# Adafruit_TMC2209_Stepper_Motor_Driver.net
KiCad netlist of a schematic drawn in EAGLE
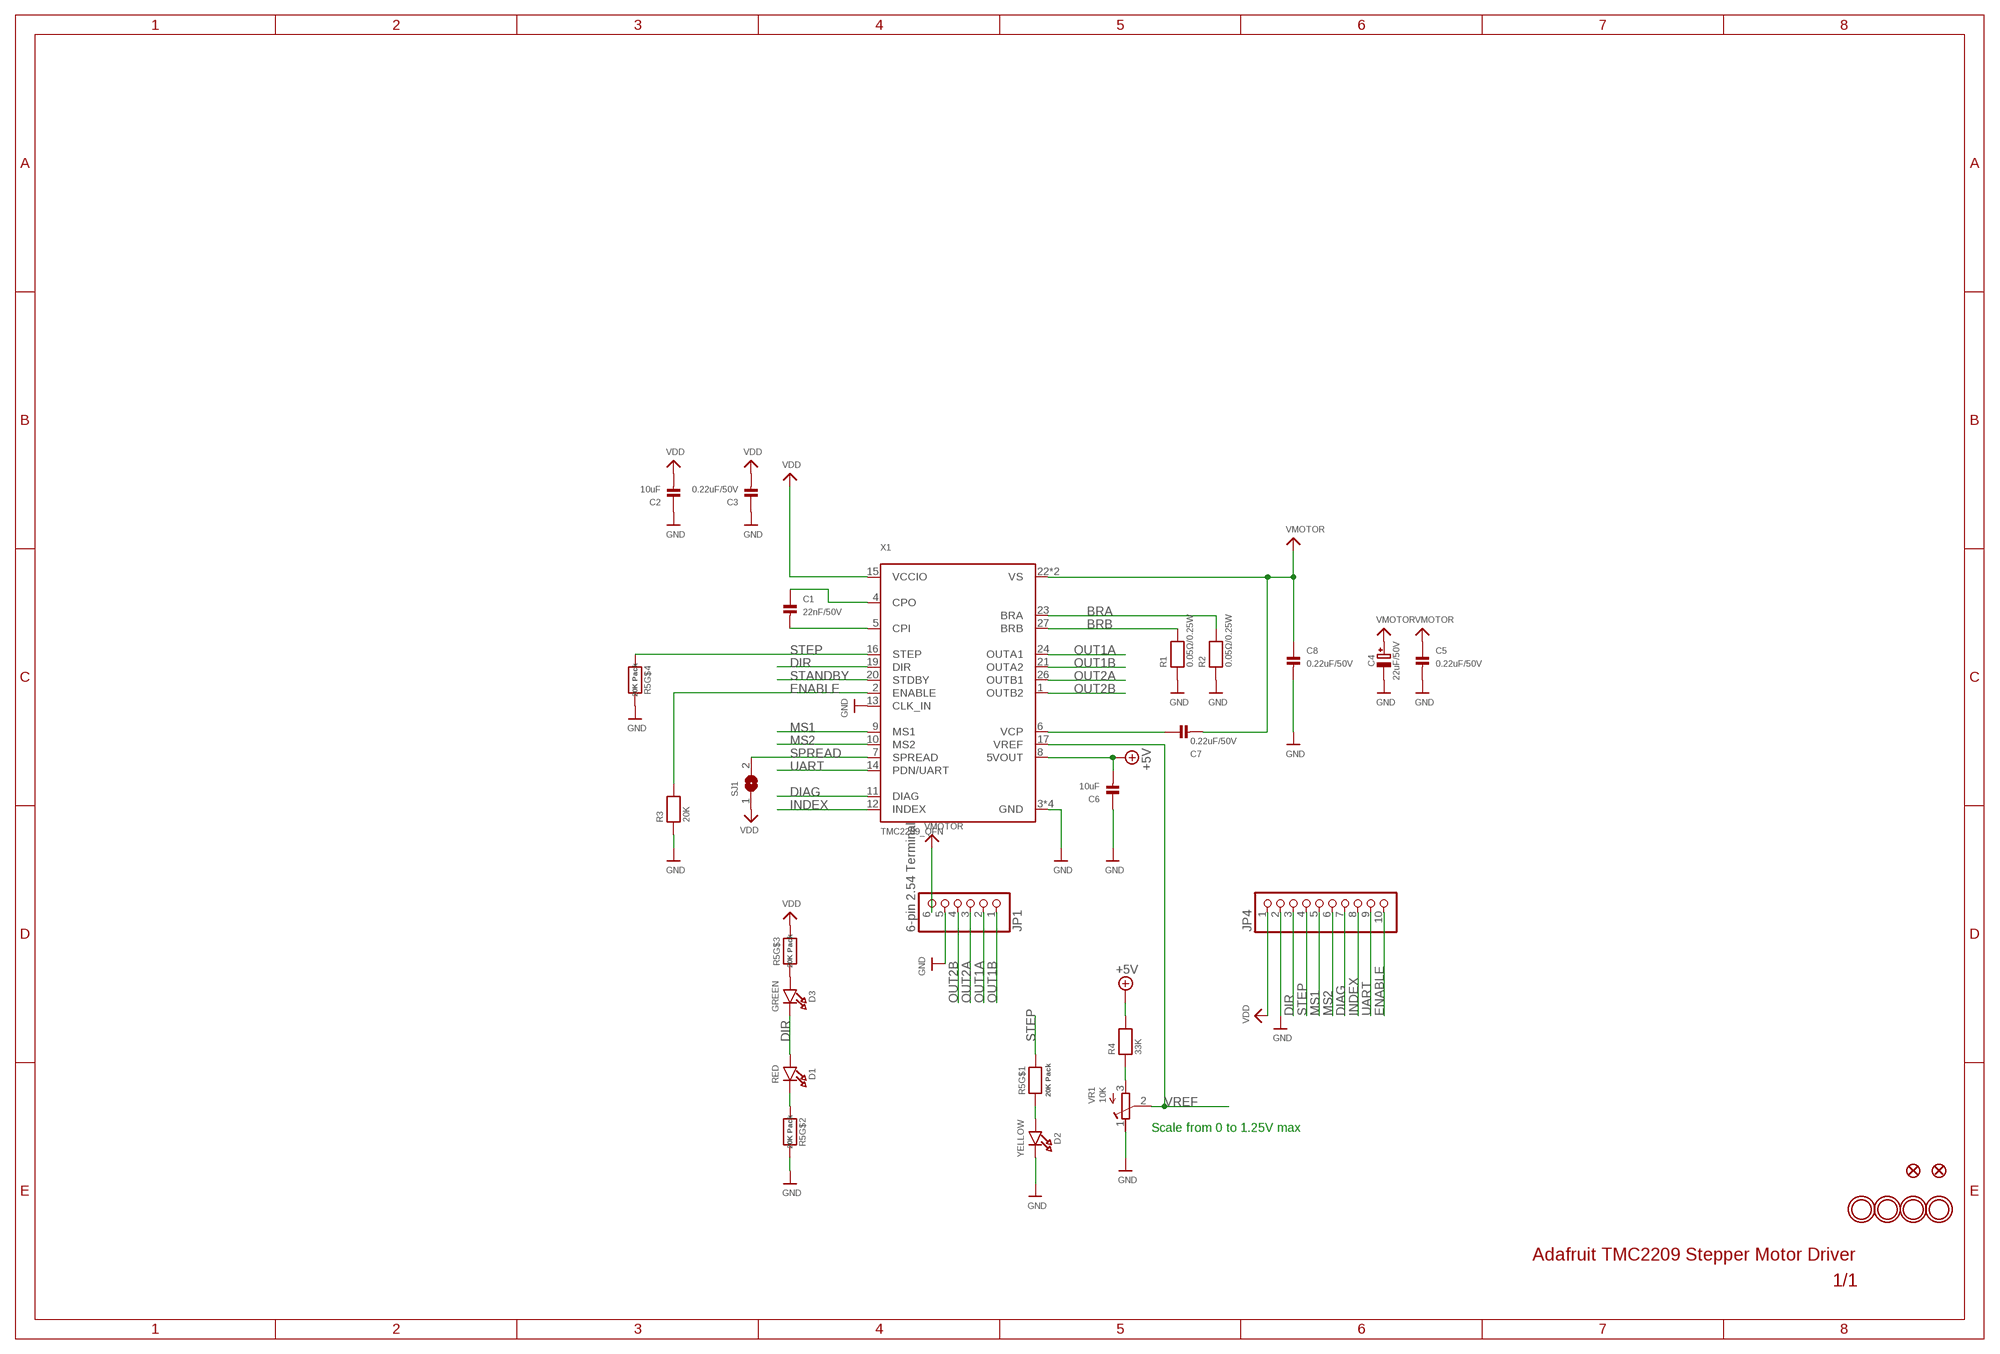
[diagram p0: schematic, sheet 1]

(export (version "E")
  (design (tool "Eeschema 10.0.6"))
  (components
    (comp (ref "C1")
      (value "22nF/50V")
      (footprint "eagle-import:0603-NO")
      (libsource (lib "eagle-import") (part "CAP_CERAMIC0603_NO"))
    )
    (comp (ref "C2")
      (value "10uF")
      (footprint "eagle-import:0805-NO")
      (libsource (lib "eagle-import") (part "CAP_CERAMIC0805-NOOUTLINE"))
    )
    (comp (ref "C3")
      (value "0.22uF/50V")
      (footprint "eagle-import:0603-NO")
      (libsource (lib "eagle-import") (part "CAP_CERAMIC0603_NO"))
    )
    (comp (ref "C4")
      (value "22uF/50V")
      (footprint "eagle-import:PANASONIC_C")
      (libsource (lib "eagle-import") (part "CAP_ELECTROLYTICPANASONIC_C"))
    )
    (comp (ref "C5")
      (value "0.22uF/50V")
      (footprint "eagle-import:0603-NO")
      (libsource (lib "eagle-import") (part "CAP_CERAMIC0603_NO"))
    )
    (comp (ref "C6")
      (value "10uF")
      (footprint "eagle-import:0805-NO")
      (libsource (lib "eagle-import") (part "CAP_CERAMIC0805-NOOUTLINE"))
    )
    (comp (ref "C7")
      (value "0.22uF/50V")
      (footprint "eagle-import:0603-NO")
      (libsource (lib "eagle-import") (part "CAP_CERAMIC0603_NO"))
    )
    (comp (ref "C8")
      (value "0.22uF/50V")
      (footprint "eagle-import:0603-NO")
      (libsource (lib "eagle-import") (part "CAP_CERAMIC0603_NO"))
    )
    (comp (ref "D1")
      (value "RED")
      (footprint "eagle-import:CHIPLED_0603_NOOUTLINE")
      (libsource (lib "eagle-import") (part "LED0603_NOOUTLINE"))
    )
    (comp (ref "D2")
      (value "YELLOW")
      (footprint "eagle-import:CHIPLED_0603_NOOUTLINE")
      (libsource (lib "eagle-import") (part "LED0603_NOOUTLINE"))
    )
    (comp (ref "D3")
      (value "GREEN")
      (footprint "eagle-import:CHIPLED_0603_NOOUTLINE")
      (libsource (lib "eagle-import") (part "LED0603_NOOUTLINE"))
    )
    (comp (ref "JP1")
      (value "6-pin 2.54 Terminal")
      (footprint "eagle-import:1X06_2.54MMTERMINAL")
      (libsource (lib "eagle-import") (part "HEADER-1X6_2.54MMTERM"))
    )
    (comp (ref "JP4")
      (value "HEADER-1X1070MIL")
      (footprint "eagle-import:1X10_ROUND70")
      (libsource (lib "eagle-import") (part "HEADER-1X1070MIL"))
    )
    (comp (ref "R1")
      (value "0.05Ω/0.25W")
      (footprint "eagle-import:0603-NO")
      (libsource (lib "eagle-import") (part "RESISTOR_0603_NOOUT"))
    )
    (comp (ref "R2")
      (value "0.05Ω/0.25W")
      (footprint "eagle-import:0603-NO")
      (libsource (lib "eagle-import") (part "RESISTOR_0603_NOOUT"))
    )
    (comp (ref "R3")
      (value "20K")
      (footprint "eagle-import:0603-NO")
      (libsource (lib "eagle-import") (part "RESISTOR_0603_NOOUT"))
    )
    (comp (ref "R4")
      (value "33K")
      (footprint "eagle-import:0603-NO")
      (libsource (lib "eagle-import") (part "RESISTOR_0603_NOOUT"))
    )
    (comp (ref "R5")
      (value "20K Pack")
      (footprint "eagle-import:RESPACK_4X0603")
      (libsource (lib "eagle-import") (part "RESISTOR_4PACK"))
    )
    (comp (ref "SJ1")
      (value "SOLDERJUMPER")
      (footprint "eagle-import:SOLDERJUMPER_ARROW_NOPASTE")
      (libsource (lib "eagle-import") (part "SOLDERJUMPER"))
    )
    (comp (ref "U$10")
      (value "FIDUCIAL_0.5MM")
      (footprint "eagle-import:FIDUCIAL_0.5MM")
      (libsource (lib "eagle-import") (part "FIDUCIAL_0.5MM"))
    )
    (comp (ref "U$11")
      (value "FIDUCIAL_0.5MM")
      (footprint "eagle-import:FIDUCIAL_0.5MM")
      (libsource (lib "eagle-import") (part "FIDUCIAL_0.5MM"))
    )
    (comp (ref "U$18")
      (value "MOUNTINGHOLE2.0")
      (footprint "eagle-import:MOUNTINGHOLE_2.0_PLATED")
      (libsource (lib "eagle-import") (part "MOUNTINGHOLE2.0"))
    )
    (comp (ref "U$22")
      (value "MOUNTINGHOLE2.0")
      (footprint "eagle-import:MOUNTINGHOLE_2.0_PLATED")
      (libsource (lib "eagle-import") (part "MOUNTINGHOLE2.0"))
    )
    (comp (ref "U$26")
      (value "MOUNTINGHOLE2.0")
      (footprint "eagle-import:MOUNTINGHOLE_2.0_PLATED")
      (libsource (lib "eagle-import") (part "MOUNTINGHOLE2.0"))
    )
    (comp (ref "U$27")
      (value "MOUNTINGHOLE2.0")
      (footprint "eagle-import:MOUNTINGHOLE_2.0_PLATED")
      (libsource (lib "eagle-import") (part "MOUNTINGHOLE2.0"))
    )
    (comp (ref "VR1")
      (value "10K")
      (footprint "eagle-import:RTRIM3314J")
      (libsource (lib "eagle-import") (part "R-TRIMM3314J"))
    )
    (comp (ref "X1")
      (value "TMC2209_QFN")
      (footprint "eagle-import:QFN28_5MM_MICROCHIP")
      (libsource (lib "eagle-import") (part "TMC2209_QFN"))
    )
  )
  (nets
    (net (code "1") (name "+5V") (class "Default")
      (node (ref "C6") (pin "2") (pinfunction "2_2") (pintype "passive"))
      (node (ref "R4") (pin "2") (pinfunction "2_2") (pintype "passive"))
      (node (ref "X1") (pin "8") (pinfunction "5VOUT_8") (pintype "bidirectional"))
    )
    (net (code "2") (name "/BRA") (class "Default")
      (node (ref "R2") (pin "2") (pinfunction "2_2") (pintype "passive"))
      (node (ref "X1") (pin "23") (pinfunction "BRA_23") (pintype "bidirectional"))
    )
    (net (code "3") (name "/BRB") (class "Default")
      (node (ref "R1") (pin "2") (pinfunction "2_2") (pintype "passive"))
      (node (ref "X1") (pin "27") (pinfunction "BRB_27") (pintype "bidirectional"))
    )
    (net (code "4") (name "/DIAG") (class "Default")
      (node (ref "JP4") (pin "7") (pinfunction "7_7") (pintype "passive"))
      (node (ref "X1") (pin "11") (pinfunction "DIAG_11") (pintype "output"))
    )
    (net (code "5") (name "/DIR") (class "Default")
      (node (ref "D1") (pin "A") (pinfunction "A_A") (pintype "passive"))
      (node (ref "D3") (pin "C") (pinfunction "C_C") (pintype "passive"))
      (node (ref "JP4") (pin "3") (pinfunction "3_3") (pintype "passive"))
      (node (ref "X1") (pin "19") (pinfunction "DIR_19") (pintype "input"))
    )
    (net (code "6") (name "/ENABLE") (class "Default")
      (node (ref "JP4") (pin "10") (pinfunction "10_10") (pintype "passive"))
      (node (ref "R3") (pin "2") (pinfunction "2_2") (pintype "passive"))
      (node (ref "X1") (pin "2") (pinfunction "ENABLE_2") (pintype "input"))
    )
    (net (code "7") (name "/INDEX") (class "Default")
      (node (ref "JP4") (pin "8") (pinfunction "8_8") (pintype "passive"))
      (node (ref "X1") (pin "12") (pinfunction "INDEX_12") (pintype "output"))
    )
    (net (code "8") (name "/MS1") (class "Default")
      (node (ref "JP4") (pin "5") (pinfunction "5_5") (pintype "passive"))
      (node (ref "X1") (pin "9") (pinfunction "MS1_9") (pintype "input"))
    )
    (net (code "9") (name "/MS2") (class "Default")
      (node (ref "JP4") (pin "6") (pinfunction "6_6") (pintype "passive"))
      (node (ref "X1") (pin "10") (pinfunction "MS2_10") (pintype "input"))
    )
    (net (code "10") (name "/OUT1A") (class "Default")
      (node (ref "JP1") (pin "2") (pinfunction "2_2") (pintype "passive"))
      (node (ref "X1") (pin "24") (pinfunction "OUTA1_24") (pintype "bidirectional"))
    )
    (net (code "11") (name "/OUT1B") (class "Default")
      (node (ref "JP1") (pin "1") (pinfunction "1_1") (pintype "passive"))
      (node (ref "X1") (pin "21") (pinfunction "OUTA2_21") (pintype "bidirectional"))
    )
    (net (code "12") (name "/OUT2A") (class "Default")
      (node (ref "JP1") (pin "3") (pinfunction "3_3") (pintype "passive"))
      (node (ref "X1") (pin "26") (pinfunction "OUTB1_26") (pintype "bidirectional"))
    )
    (net (code "13") (name "/OUT2B") (class "Default")
      (node (ref "JP1") (pin "4") (pinfunction "4_4") (pintype "passive"))
      (node (ref "X1") (pin "1") (pinfunction "OUTB2_1") (pintype "bidirectional"))
    )
    (net (code "14") (name "/SPREAD") (class "Default")
      (node (ref "SJ1") (pin "2") (pinfunction "2_2") (pintype "passive"))
      (node (ref "X1") (pin "7") (pinfunction "SPREAD_7") (pintype "input"))
    )
    (net (code "15") (name "/STANDBY") (class "Default")
      (node (ref "X1") (pin "20") (pinfunction "STDBY_20") (pintype "bidirectional"))
    )
    (net (code "16") (name "/STEP") (class "Default")
      (node (ref "JP4") (pin "4") (pinfunction "4_4") (pintype "passive"))
      (node (ref "R5") (pin "4") (pinfunction "1_4") (pintype "passive"))
      (node (ref "R5") (pin "8") (pinfunction "2_8") (pintype "passive"))
      (node (ref "X1") (pin "16") (pinfunction "STEP_16") (pintype "input"))
    )
    (net (code "17") (name "/UART") (class "Default")
      (node (ref "JP4") (pin "9") (pinfunction "9_9") (pintype "passive"))
      (node (ref "X1") (pin "14") (pinfunction "PDN/UART_14") (pintype "bidirectional"))
    )
    (net (code "18") (name "/VREF") (class "Default")
      (node (ref "VR1") (pin "2") (pinfunction "S_2") (pintype "passive"))
      (node (ref "X1") (pin "17") (pinfunction "VREF_17") (pintype "bidirectional"))
    )
    (net (code "19") (name "GND") (class "Default")
      (node (ref "C2") (pin "1") (pinfunction "1_1") (pintype "passive"))
      (node (ref "C3") (pin "1") (pinfunction "1_1") (pintype "passive"))
      (node (ref "C4") (pin "-") (pinfunction "-_-") (pintype "passive"))
      (node (ref "C5") (pin "2") (pinfunction "2_2") (pintype "passive"))
      (node (ref "C6") (pin "1") (pinfunction "1_1") (pintype "passive"))
      (node (ref "C8") (pin "2") (pinfunction "2_2") (pintype "passive"))
      (node (ref "D2") (pin "C") (pinfunction "C_C") (pintype "passive"))
      (node (ref "JP1") (pin "5") (pinfunction "5_5") (pintype "passive"))
      (node (ref "JP4") (pin "2") (pinfunction "2_2") (pintype "passive"))
      (node (ref "R1") (pin "1") (pinfunction "1_1") (pintype "passive"))
      (node (ref "R2") (pin "1") (pinfunction "1_1") (pintype "passive"))
      (node (ref "R3") (pin "1") (pinfunction "1_1") (pintype "passive"))
      (node (ref "R5") (pin "5") (pinfunction "2_5") (pintype "passive"))
      (node (ref "R5") (pin "7") (pinfunction "2_7") (pintype "passive"))
      (node (ref "VR1") (pin "1") (pinfunction "E_1") (pintype "passive"))
      (node (ref "X1") (pin "13") (pinfunction "CLK_IN_13") (pintype "input"))
      (node (ref "X1") (pin "18") (pinfunction "GND_18") (pintype "power_in"))
      (node (ref "X1") (pin "25") (pinfunction "GND_25") (pintype "power_in"))
      (node (ref "X1") (pin "3") (pinfunction "GND_3") (pintype "power_in"))
      (node (ref "X1") (pin "THERMAL") (pinfunction "GND_THERMAL") (pintype "power_in"))
    )
    (net (code "20") (name "Net-(D2-PadA)") (class "Default")
      (node (ref "D2") (pin "A") (pinfunction "A_A") (pintype "passive"))
      (node (ref "R5") (pin "1") (pinfunction "1_1") (pintype "passive"))
    )
    (net (code "21") (name "Net-(R5B-1)") (class "Default")
      (node (ref "D1") (pin "C") (pinfunction "C_C") (pintype "passive"))
      (node (ref "R5") (pin "2") (pinfunction "1_2") (pintype "passive"))
    )
    (net (code "22") (name "Net-(R5C-1)") (class "Default")
      (node (ref "D3") (pin "A") (pinfunction "A_A") (pintype "passive"))
      (node (ref "R5") (pin "3") (pinfunction "1_3") (pintype "passive"))
    )
    (net (code "23") (name "Net-(VR1-A)") (class "Default")
      (node (ref "R4") (pin "1") (pinfunction "1_1") (pintype "passive"))
      (node (ref "VR1") (pin "3") (pinfunction "A_3") (pintype "passive"))
    )
    (net (code "24") (name "Net-(X1-CPI)") (class "Default")
      (node (ref "C1") (pin "2") (pinfunction "2_2") (pintype "passive"))
      (node (ref "X1") (pin "5") (pinfunction "CPI_5") (pintype "bidirectional"))
    )
    (net (code "25") (name "Net-(X1-CPO)") (class "Default")
      (node (ref "C1") (pin "1") (pinfunction "1_1") (pintype "passive"))
      (node (ref "X1") (pin "4") (pinfunction "CPO_4") (pintype "bidirectional"))
    )
    (net (code "26") (name "Net-(X1-VCP)") (class "Default")
      (node (ref "C7") (pin "1") (pinfunction "1_1") (pintype "passive"))
      (node (ref "X1") (pin "6") (pinfunction "VCP_6") (pintype "bidirectional"))
    )
    (net (code "27") (name "VDD") (class "Default")
      (node (ref "C2") (pin "2") (pinfunction "2_2") (pintype "passive"))
      (node (ref "C3") (pin "2") (pinfunction "2_2") (pintype "passive"))
      (node (ref "JP4") (pin "1") (pinfunction "1_1") (pintype "passive"))
      (node (ref "R5") (pin "6") (pinfunction "2_6") (pintype "passive"))
      (node (ref "SJ1") (pin "1") (pinfunction "1_1") (pintype "passive"))
      (node (ref "X1") (pin "15") (pinfunction "VCCIO_15") (pintype "bidirectional"))
    )
    (net (code "28") (name "VMOTOR") (class "Default")
      (node (ref "C4") (pin "+") (pinfunction "+_+") (pintype "passive"))
      (node (ref "C5") (pin "1") (pinfunction "1_1") (pintype "passive"))
      (node (ref "C7") (pin "2") (pinfunction "2_2") (pintype "passive"))
      (node (ref "C8") (pin "1") (pinfunction "1_1") (pintype "passive"))
      (node (ref "JP1") (pin "6") (pinfunction "6_6") (pintype "passive"))
      (node (ref "X1") (pin "22") (pinfunction "VS_22") (pintype "bidirectional"))
      (node (ref "X1") (pin "28") (pinfunction "VS_28") (pintype "bidirectional"))
    )
  )
)
